# LCDTFT_FPCADPTR40T50P.net
KiCad netlist of a schematic drawn in Altium Designer
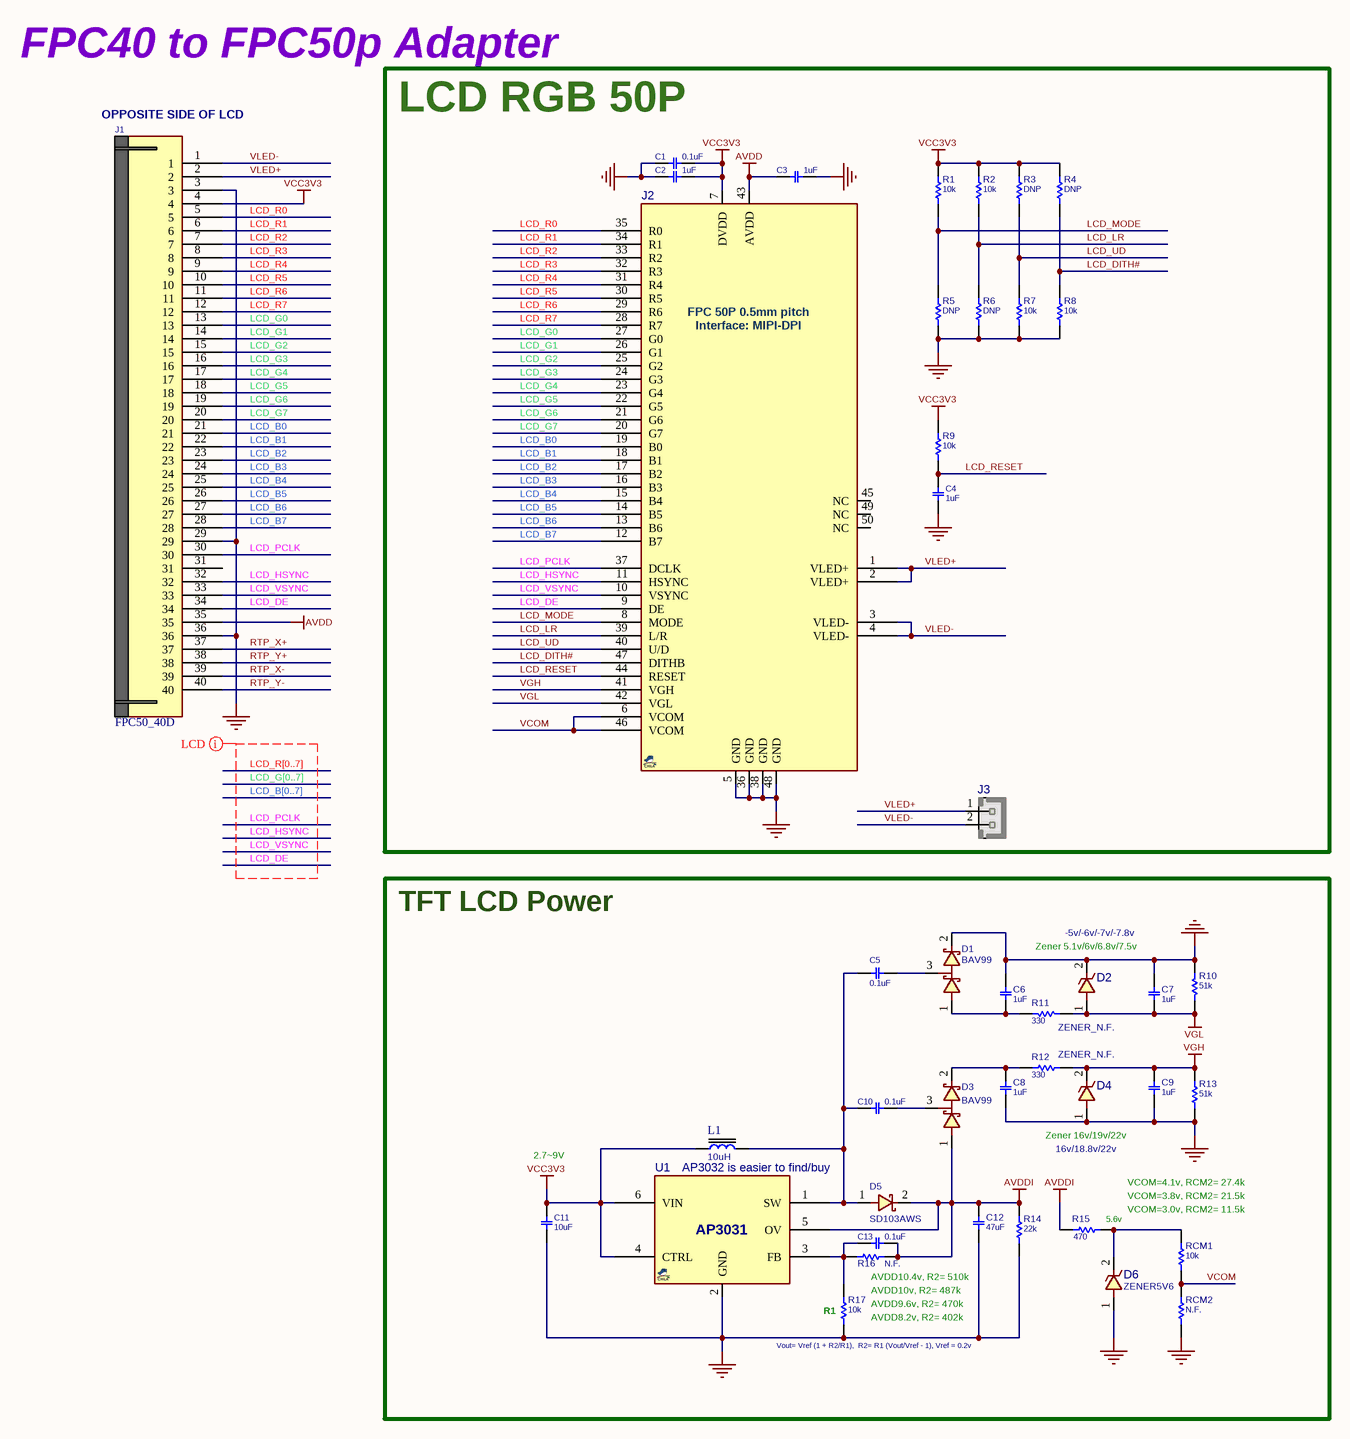
[diagram p0: LCDTFT_FPCADPTR40T50P.SchDoc]

(export (version "E")
  (design (tool "Eeschema 10.0.6"))
  (components
    (comp (ref "C1")
      (value "0.1uF")
      (footprint "C0402")
      (description "CAP, MLCC")
      (fields (field (name "MANF_P#") "GRM155R71H104KE14D") (field (name "MANF") "Murata"))
      (libsource (lib "passive_smd") (part "CAP_SMD_MLCC"))
    )
    (comp (ref "C2")
      (value "1uF")
      (footprint "C0402")
      (description "CAP, MLCC")
      (fields (field (name "MANF_P#") "CL05A105KO5NNND") (field (name "MANF") "Samsung"))
      (libsource (lib "passive_smd") (part "CAP_SMD_MLCC"))
    )
    (comp (ref "C3")
      (value "1uF")
      (footprint "C0402")
      (description "CAP, MLCC")
      (fields (field (name "MANF_P#") "CL05A105KO5NNND") (field (name "MANF") "Samsung"))
      (libsource (lib "passive_smd") (part "CAP_SMD_MLCC"))
    )
    (comp (ref "C4")
      (value "1uF")
      (footprint "C0402")
      (description "CAP, MLCC")
      (fields (field (name "MANF_P#") "CL05A105KO5NNND") (field (name "MANF") "Samsung"))
      (libsource (lib "passive_smd") (part "CAP_SMD_MLCC"))
    )
    (comp (ref "C5")
      (value "0.1uF")
      (footprint "C0402")
      (description "CAP, MLCC, 100nF, 50V, X7R, 10%, 0402C")
      (fields (field (name "MANF") "Murata") (field (name "MANF_P#") "GCM155R71H104KE02D"))
      (libsource (lib "passive_mlcc_smd") (part "CAP_SMD_MLCC_100n50V"))
    )
    (comp (ref "C6")
      (value "1uF")
      (footprint "C0603")
      (description "CAP, MLCC")
      (fields (field (name "MANF_P#") "CL10A105KB8NNNC") (field (name "MANF") "Samsung"))
      (libsource (lib "passive_smd") (part "CAP_SMD_MLCC"))
    )
    (comp (ref "C7")
      (value "1uF")
      (footprint "C0603")
      (description "CAP, MLCC")
      (fields (field (name "MANF_P#") "CL10A105KB8NNNC") (field (name "MANF") "Samsung"))
      (libsource (lib "passive_smd") (part "CAP_SMD_MLCC"))
    )
    (comp (ref "C8")
      (value "1uF")
      (footprint "C0603")
      (description "CAP, MLCC")
      (fields (field (name "MANF_P#") "CL10A105KB8NNNC") (field (name "MANF") "Samsung"))
      (libsource (lib "passive_smd") (part "CAP_SMD_MLCC"))
    )
    (comp (ref "C9")
      (value "1uF")
      (footprint "C0603")
      (description "CAP, MLCC")
      (fields (field (name "MANF_P#") "CL10A105KB8NNNC") (field (name "MANF") "Samsung"))
      (libsource (lib "passive_smd") (part "CAP_SMD_MLCC"))
    )
    (comp (ref "C10")
      (value "0.1uF")
      (footprint "C0402")
      (description "CAP, MLCC, 100nF, 50V, X7R, 10%, 0402C")
      (fields (field (name "MANF") "Murata") (field (name "MANF_P#") "GCM155R71H104KE02D"))
      (libsource (lib "passive_mlcc_smd") (part "CAP_SMD_MLCC_100n50V"))
    )
    (comp (ref "C11")
      (value "10uF")
      (footprint "C0603")
      (description "CAP, MLCC")
      (fields (field (name "MANF_P#") "CL10A106MO8NQNC") (field (name "MANF") "Samsung"))
      (libsource (lib "passive_smd") (part "CAP_SMD_MLCC"))
    )
    (comp (ref "C12")
      (value "47uF")
      (footprint "C1206")
      (description "CAP, MLCC")
      (fields (field (name "MANF_P#") "GRM31CR61E476ME44L") (field (name "MANF") "Murata"))
      (libsource (lib "passive_smd") (part "CAP_SMD_MLCC"))
    )
    (comp (ref "C13")
      (value "0.1uF")
      (footprint "C0402")
      (description "CAP, MLCC, 100nF, 50V, X7R, 10%, 0402C")
      (fields (field (name "MANF") "Murata") (field (name "MANF_P#") "GCM155R71H104KE02D"))
      (libsource (lib "passive_mlcc_smd") (part "CAP_SMD_MLCC_100n50V"))
    )
    (comp (ref "D1")
      (value "BAV99")
      (footprint "SOT23_3")
      (description "DIODE, SCHOTTKY, DUAL, 30V, 0.2A")
      (fields (field (name "MANF") "Diodes"))
      (libsource (lib "diode") (part "DIODE_SMD_SCHOTTKY_BAV99"))
    )
    (comp (ref "D2")
      (value "ZENER_N.F.")
      (footprint "D_SOD123W")
      (description "DIODE, ZENER, 0.5W")
      (fields (field (name "MANF") "Diodes"))
      (libsource (lib "diode") (part "DIODE_SMD_ZENER_DFLZ5V1"))
    )
    (comp (ref "D3")
      (value "BAV99")
      (footprint "SOT23_3")
      (description "DIODE, SCHOTTKY, DUAL, 30V, 0.2A")
      (fields (field (name "MANF") "Diodes"))
      (libsource (lib "diode") (part "DIODE_SMD_SCHOTTKY_BAV99"))
    )
    (comp (ref "D4")
      (value "ZENER_N.F.")
      (footprint "D_SOD123W")
      (description "DIODE, ZENER, 0.5W")
      (fields (field (name "MANF") "Diodes"))
      (libsource (lib "diode") (part "DIODE_SMD_ZENER_DFLZ5V1"))
    )
    (comp (ref "D5")
      (value "SD103AWS")
      (footprint "D_SOD323")
      (description "DIODE, SCHOTTKY, 40V, 2A")
      (fields (field (name "MANF") "DIODES"))
      (libsource (lib "diode") (part "DIODE_SMD_SCHOTTKY_1N5819"))
    )
    (comp (ref "D6")
      (value "ZENER5V6")
      (footprint "D_SOD123W")
      (description "DIODE, ZENER, 0.5W")
      (fields (field (name "MANF") "Diodes"))
      (libsource (lib "diode") (part "DIODE_SMD_ZENER_DFLZ5V1"))
    )
    (comp (ref "J1")
      (value "FPC50_40D")
      (footprint "FPC50_40D_FFC2B29")
      (description "CONN, FPC, 0.50mm pitch, RightAngle, Dual side Contact")
      (fields (field (name "MANF") "GCT") (field (name "MANF_P#") "FFC2B29-40-G"))
      (libsource (lib "conn_fpc") (part "FPC50_40D_FFC2B29"))
    )
    (comp (ref "J2")
      (value "FPC_50_0.5mm")
      (footprint "FPC50_50T")
      (description "LCD TFT Color, FPC50P, RGB")
      (libsource (lib "lcdtft") (part "LCDTFT_DPI_FPC50P"))
    )
    (comp (ref "J3")
      (value "HHDR_2")
      (footprint "ER_CON3P5_2_SMD")
      (description "JST-XH pitch: 2.5mm")
      (libsource (lib "conn_wire2board") (part "XH_2"))
    )
    (comp (ref "L1")
      (value "10uH")
      (footprint "L_4")
      (description "INDUCTOR, POWER, SMD")
      (fields (field (name "MANF_P#") "GCD43-100MC"))
      (libsource (lib "passive") (part "INDPWR_SMD"))
    )
    (comp (ref "R1")
      (value "10k")
      (footprint "R0402")
      (description "RESISTOR, SMD")
      (libsource (lib "passive_res_smd") (part "RES_SMD"))
    )
    (comp (ref "R2")
      (value "10k")
      (footprint "R0402")
      (description "RESISTOR, SMD")
      (libsource (lib "passive_res_smd") (part "RES_SMD"))
    )
    (comp (ref "R3")
      (value "DNP")
      (footprint "R0402")
      (description "RESISTOR, SMD")
      (libsource (lib "passive_res_smd") (part "RES_SMD"))
    )
    (comp (ref "R4")
      (value "DNP")
      (footprint "R0402")
      (description "RESISTOR, SMD")
      (libsource (lib "passive_res_smd") (part "RES_SMD"))
    )
    (comp (ref "R5")
      (value "DNP")
      (footprint "R0402")
      (description "RESISTOR, SMD")
      (libsource (lib "passive_res_smd") (part "RES_SMD"))
    )
    (comp (ref "R6")
      (value "DNP")
      (footprint "R0402")
      (description "RESISTOR, SMD")
      (libsource (lib "passive_res_smd") (part "RES_SMD"))
    )
    (comp (ref "R7")
      (value "10k")
      (footprint "R0402")
      (description "RESISTOR, SMD")
      (libsource (lib "passive_res_smd") (part "RES_SMD"))
    )
    (comp (ref "R8")
      (value "10k")
      (footprint "R0402")
      (description "RESISTOR, SMD")
      (libsource (lib "passive_res_smd") (part "RES_SMD"))
    )
    (comp (ref "R9")
      (value "10k")
      (footprint "R0402")
      (description "RESISTOR, SMD")
      (libsource (lib "passive_res_smd") (part "RES_SMD"))
    )
    (comp (ref "R10")
      (value "51k")
      (footprint "R0402")
      (description "RESISTOR, SMD, 20K, 0402")
      (fields (field (name "MANF") "Yageo") (field (name "MANF_P#") "RK73H1ETTP2002F"))
      (libsource (lib "chila_passive") (part "RES_SMD"))
    )
    (comp (ref "R11")
      (value "330")
      (footprint "R0402")
      (description "RESISTOR, SMD, 20K, 0402")
      (fields (field (name "MANF") "Yageo") (field (name "MANF_P#") "RK73H1ETTP2002F"))
      (libsource (lib "chila_passive") (part "RES_SMD"))
    )
    (comp (ref "R12")
      (value "330")
      (footprint "R0402")
      (description "RESISTOR, SMD, 20K, 0402")
      (fields (field (name "MANF") "Yageo") (field (name "MANF_P#") "RK73H1ETTP2002F"))
      (libsource (lib "chila_passive") (part "RES_SMD"))
    )
    (comp (ref "R13")
      (value "51k")
      (footprint "R0402")
      (description "RESISTOR, SMD, 20K, 0402")
      (fields (field (name "MANF") "Yageo") (field (name "MANF_P#") "RK73H1ETTP2002F"))
      (libsource (lib "chila_passive") (part "RES_SMD"))
    )
    (comp (ref "R14")
      (value "22k")
      (footprint "R0402")
      (description "RESISTOR, SMD, 20K, 0402")
      (fields (field (name "MANF") "Yageo") (field (name "MANF_P#") "RK73H1ETTP2002F"))
      (libsource (lib "chila_passive") (part "RES_SMD"))
    )
    (comp (ref "R15")
      (value "470")
      (footprint "R0402")
      (description "RESISTOR, SMD, 20K, 0402")
      (fields (field (name "MANF") "Yageo") (field (name "MANF_P#") "RK73H1ETTP2002F"))
      (libsource (lib "chila_passive") (part "RES_SMD"))
    )
    (comp (ref "R16")
      (value "N.F.")
      (footprint "R0402")
      (description "RESISTOR, SMD, 20K, 0402")
      (fields (field (name "MANF") "Yageo") (field (name "MANF_P#") "RK73H1ETTP2002F"))
      (libsource (lib "chila_passive") (part "RES_SMD"))
    )
    (comp (ref "R17")
      (value "10k")
      (footprint "R0402")
      (description "RESISTOR, SMD, 20K, 0402")
      (fields (field (name "MANF") "Yageo") (field (name "MANF_P#") "RK73H1ETTP2002F"))
      (libsource (lib "chila_passive") (part "RES_SMD"))
    )
    (comp (ref "RCM1")
      (value "10k")
      (footprint "R0402")
      (description "RESISTOR, SMD, 20K, 0402")
      (fields (field (name "MANF") "Yageo") (field (name "MANF_P#") "RK73H1ETTP2002F"))
      (libsource (lib "chila_passive") (part "RES_SMD"))
    )
    (comp (ref "RCM2")
      (value "N.F.")
      (footprint "R0402")
      (description "RESISTOR, SMD, 20K, 0402")
      (fields (field (name "MANF") "Yageo") (field (name "MANF_P#") "RK73H1ETTP2002F"))
      (libsource (lib "chila_passive") (part "RES_SMD"))
    )
    (comp (ref "U1")
      (value "AP3031")
      (footprint "SOT23_6")
      (description "REG, Switching, Boost, 1.4A, ADJ, 1MHz, SOT-23-6")
      (fields (field (name "MANF_P#") "AP3031K") (field (name "MANF") "Diodes"))
      (libsource (lib "pwr_switching_boost") (part "VREG_AP3031_SOT23"))
    )
  )
  (nets
    (net (code "1") (name "/LCD_B0") (class "Default")
      (node (ref "J1") (pin "21") (pinfunction "21_21") (pintype "passive"))
      (node (ref "J2") (pin "19") (pinfunction "B0_19") (pintype "passive"))
    )
    (net (code "2") (name "/LCD_B1") (class "Default")
      (node (ref "J1") (pin "22") (pinfunction "22_22") (pintype "passive"))
      (node (ref "J2") (pin "18") (pinfunction "B1_18") (pintype "passive"))
    )
    (net (code "3") (name "/LCD_B2") (class "Default")
      (node (ref "J1") (pin "23") (pinfunction "23_23") (pintype "passive"))
      (node (ref "J2") (pin "17") (pinfunction "B2_17") (pintype "passive"))
    )
    (net (code "4") (name "/LCD_B3") (class "Default")
      (node (ref "J1") (pin "24") (pinfunction "24_24") (pintype "passive"))
      (node (ref "J2") (pin "16") (pinfunction "B3_16") (pintype "passive"))
    )
    (net (code "5") (name "/LCD_B4") (class "Default")
      (node (ref "J1") (pin "25") (pinfunction "25_25") (pintype "passive"))
      (node (ref "J2") (pin "15") (pinfunction "B4_15") (pintype "passive"))
    )
    (net (code "6") (name "/LCD_B5") (class "Default")
      (node (ref "J1") (pin "26") (pinfunction "26_26") (pintype "passive"))
      (node (ref "J2") (pin "14") (pinfunction "B5_14") (pintype "passive"))
    )
    (net (code "7") (name "/LCD_B6") (class "Default")
      (node (ref "J1") (pin "27") (pinfunction "27_27") (pintype "passive"))
      (node (ref "J2") (pin "13") (pinfunction "B6_13") (pintype "passive"))
    )
    (net (code "8") (name "/LCD_B7") (class "Default")
      (node (ref "J1") (pin "28") (pinfunction "28_28") (pintype "passive"))
      (node (ref "J2") (pin "12") (pinfunction "B7_12") (pintype "passive"))
    )
    (net (code "10") (name "/LCD_DE") (class "Default")
      (node (ref "J1") (pin "34") (pinfunction "34_34") (pintype "passive"))
      (node (ref "J2") (pin "9") (pinfunction "DE_9") (pintype "passive"))
    )
    (net (code "11") (name "/LCD_DITH#") (class "Default")
      (node (ref "J2") (pin "47") (pinfunction "DITHB_47") (pintype "passive"))
      (node (ref "R4") (pin "2") (pinfunction "2_2") (pintype "passive"))
      (node (ref "R8") (pin "1") (pinfunction "1_1") (pintype "passive"))
    )
    (net (code "12") (name "/LCD_G0") (class "Default")
      (node (ref "J1") (pin "13") (pinfunction "13_13") (pintype "passive"))
      (node (ref "J2") (pin "27") (pinfunction "G0_27") (pintype "passive"))
    )
    (net (code "13") (name "/LCD_G1") (class "Default")
      (node (ref "J1") (pin "14") (pinfunction "14_14") (pintype "passive"))
      (node (ref "J2") (pin "26") (pinfunction "G1_26") (pintype "passive"))
    )
    (net (code "14") (name "/LCD_G2") (class "Default")
      (node (ref "J1") (pin "15") (pinfunction "15_15") (pintype "passive"))
      (node (ref "J2") (pin "25") (pinfunction "G2_25") (pintype "passive"))
    )
    (net (code "15") (name "/LCD_G3") (class "Default")
      (node (ref "J1") (pin "16") (pinfunction "16_16") (pintype "passive"))
      (node (ref "J2") (pin "24") (pinfunction "G3_24") (pintype "passive"))
    )
    (net (code "16") (name "/LCD_G4") (class "Default")
      (node (ref "J1") (pin "17") (pinfunction "17_17") (pintype "passive"))
      (node (ref "J2") (pin "23") (pinfunction "G4_23") (pintype "passive"))
    )
    (net (code "17") (name "/LCD_G5") (class "Default")
      (node (ref "J1") (pin "18") (pinfunction "18_18") (pintype "passive"))
      (node (ref "J2") (pin "22") (pinfunction "G5_22") (pintype "passive"))
    )
    (net (code "18") (name "/LCD_G6") (class "Default")
      (node (ref "J1") (pin "19") (pinfunction "19_19") (pintype "passive"))
      (node (ref "J2") (pin "21") (pinfunction "G6_21") (pintype "passive"))
    )
    (net (code "19") (name "/LCD_G7") (class "Default")
      (node (ref "J1") (pin "20") (pinfunction "20_20") (pintype "passive"))
      (node (ref "J2") (pin "20") (pinfunction "G7_20") (pintype "passive"))
    )
    (net (code "21") (name "/LCD_HSYNC") (class "Default")
      (node (ref "J1") (pin "32") (pinfunction "32_32") (pintype "passive"))
      (node (ref "J2") (pin "11") (pinfunction "HSYNC_11") (pintype "passive"))
    )
    (net (code "22") (name "/LCD_LR") (class "Default")
      (node (ref "J2") (pin "39") (pinfunction "L/R_39") (pintype "passive"))
      (node (ref "R2") (pin "2") (pinfunction "2_2") (pintype "passive"))
      (node (ref "R6") (pin "1") (pinfunction "1_1") (pintype "passive"))
    )
    (net (code "23") (name "/LCD_MODE") (class "Default")
      (node (ref "J2") (pin "8") (pinfunction "MODE_8") (pintype "passive"))
      (node (ref "R1") (pin "2") (pinfunction "2_2") (pintype "passive"))
      (node (ref "R5") (pin "1") (pinfunction "1_1") (pintype "passive"))
    )
    (net (code "24") (name "/LCD_PCLK") (class "Default")
      (node (ref "J1") (pin "30") (pinfunction "30_30") (pintype "passive"))
      (node (ref "J2") (pin "37") (pinfunction "DCLK_37") (pintype "passive"))
    )
    (net (code "25") (name "/LCD_R0") (class "Default")
      (node (ref "J1") (pin "5") (pinfunction "5_5") (pintype "passive"))
      (node (ref "J2") (pin "35") (pinfunction "R0_35") (pintype "passive"))
    )
    (net (code "26") (name "/LCD_R1") (class "Default")
      (node (ref "J1") (pin "6") (pinfunction "6_6") (pintype "passive"))
      (node (ref "J2") (pin "34") (pinfunction "R1_34") (pintype "passive"))
    )
    (net (code "27") (name "/LCD_R2") (class "Default")
      (node (ref "J1") (pin "7") (pinfunction "7_7") (pintype "passive"))
      (node (ref "J2") (pin "33") (pinfunction "R2_33") (pintype "passive"))
    )
    (net (code "28") (name "/LCD_R3") (class "Default")
      (node (ref "J1") (pin "8") (pinfunction "8_8") (pintype "passive"))
      (node (ref "J2") (pin "32") (pinfunction "R3_32") (pintype "passive"))
    )
    (net (code "29") (name "/LCD_R4") (class "Default")
      (node (ref "J1") (pin "9") (pinfunction "9_9") (pintype "passive"))
      (node (ref "J2") (pin "31") (pinfunction "R4_31") (pintype "passive"))
    )
    (net (code "30") (name "/LCD_R5") (class "Default")
      (node (ref "J1") (pin "10") (pinfunction "10_10") (pintype "passive"))
      (node (ref "J2") (pin "30") (pinfunction "R5_30") (pintype "passive"))
    )
    (net (code "31") (name "/LCD_R6") (class "Default")
      (node (ref "J1") (pin "11") (pinfunction "11_11") (pintype "passive"))
      (node (ref "J2") (pin "29") (pinfunction "R6_29") (pintype "passive"))
    )
    (net (code "32") (name "/LCD_R7") (class "Default")
      (node (ref "J1") (pin "12") (pinfunction "12_12") (pintype "passive"))
      (node (ref "J2") (pin "28") (pinfunction "R7_28") (pintype "passive"))
    )
    (net (code "33") (name "/LCD_RESET") (class "Default")
      (node (ref "C4") (pin "1") (pinfunction "1_1") (pintype "passive"))
      (node (ref "J2") (pin "44") (pinfunction "RESET_44") (pintype "passive"))
      (node (ref "R9") (pin "2") (pinfunction "2_2") (pintype "passive"))
    )
    (net (code "35") (name "/LCD_UD") (class "Default")
      (node (ref "J2") (pin "40") (pinfunction "U/D_40") (pintype "passive"))
      (node (ref "R3") (pin "2") (pinfunction "2_2") (pintype "passive"))
      (node (ref "R7") (pin "1") (pinfunction "1_1") (pintype "passive"))
    )
    (net (code "36") (name "/LCD_VSYNC") (class "Default")
      (node (ref "J1") (pin "33") (pinfunction "33_33") (pintype "passive"))
      (node (ref "J2") (pin "10") (pinfunction "VSYNC_10") (pintype "passive"))
    )
    (net (code "37") (name "/RTP_X+") (class "Default")
      (node (ref "J1") (pin "37") (pinfunction "37_37") (pintype "passive"))
    )
    (net (code "38") (name "/RTP_X-") (class "Default")
      (node (ref "J1") (pin "39") (pinfunction "39_39") (pintype "passive"))
    )
    (net (code "39") (name "/RTP_Y+") (class "Default")
      (node (ref "J1") (pin "38") (pinfunction "38_38") (pintype "passive"))
    )
    (net (code "40") (name "/RTP_Y-") (class "Default")
      (node (ref "J1") (pin "40") (pinfunction "40_40") (pintype "passive"))
    )
    (net (code "41") (name "/VCOM") (class "Default")
      (node (ref "J2") (pin "46") (pinfunction "VCOM_46") (pintype "passive"))
      (node (ref "J2") (pin "6") (pinfunction "VCOM_6") (pintype "passive"))
      (node (ref "RCM1") (pin "2") (pinfunction "2_2") (pintype "passive"))
      (node (ref "RCM2") (pin "1") (pinfunction "1_1") (pintype "passive"))
    )
    (net (code "42") (name "/VLED+") (class "Default")
      (node (ref "J1") (pin "2") (pinfunction "2_2") (pintype "passive"))
      (node (ref "J2") (pin "1") (pinfunction "VLED+_1") (pintype "passive"))
      (node (ref "J2") (pin "2") (pinfunction "VLED+_2") (pintype "passive"))
      (node (ref "J3") (pin "1") (pinfunction "1_1") (pintype "passive"))
    )
    (net (code "43") (name "/VLED-") (class "Default")
      (node (ref "J1") (pin "1") (pinfunction "1_1") (pintype "passive"))
      (node (ref "J2") (pin "3") (pinfunction "VLED-_3") (pintype "passive"))
      (node (ref "J2") (pin "4") (pinfunction "VLED-_4") (pintype "passive"))
      (node (ref "J3") (pin "2") (pinfunction "2_2") (pintype "passive"))
    )
    (net (code "44") (name "AVDD") (class "Default")
      (node (ref "C3") (pin "2") (pinfunction "2_2") (pintype "passive"))
      (node (ref "J1") (pin "35") (pinfunction "35_35") (pintype "passive"))
      (node (ref "J2") (pin "43") (pinfunction "AVDD_43") (pintype "passive"))
    )
    (net (code "45") (name "AVDDI") (class "Default")
      (node (ref "C12") (pin "2") (pinfunction "2_2") (pintype "passive"))
      (node (ref "C13") (pin "1") (pinfunction "1_1") (pintype "passive"))
      (node (ref "D3") (pin "1") (pinfunction "1_1") (pintype "passive"))
      (node (ref "D5") (pin "2") (pinfunction "2_2") (pintype "passive"))
      (node (ref "R14") (pin "1") (pinfunction "1_1") (pintype "passive"))
      (node (ref "R15") (pin "1") (pinfunction "1_1") (pintype "passive"))
      (node (ref "R16") (pin "2") (pinfunction "2_2") (pintype "passive"))
      (node (ref "U1") (pin "5") (pinfunction "OV_5") (pintype "passive"))
    )
    (net (code "46") (name "GND") (class "Default")
      (node (ref "C1") (pin "2") (pinfunction "2_2") (pintype "passive"))
      (node (ref "C11") (pin "1") (pinfunction "1_1") (pintype "passive"))
      (node (ref "C12") (pin "1") (pinfunction "1_1") (pintype "passive"))
      (node (ref "C2") (pin "2") (pinfunction "2_2") (pintype "passive"))
      (node (ref "C3") (pin "1") (pinfunction "1_1") (pintype "passive"))
      (node (ref "C4") (pin "2") (pinfunction "2_2") (pintype "passive"))
      (node (ref "C6") (pin "1") (pinfunction "1_1") (pintype "passive"))
      (node (ref "C7") (pin "1") (pinfunction "1_1") (pintype "passive"))
      (node (ref "C8") (pin "1") (pinfunction "1_1") (pintype "passive"))
      (node (ref "C9") (pin "1") (pinfunction "1_1") (pintype "passive"))
      (node (ref "D1") (pin "2") (pinfunction "2_2") (pintype "passive"))
      (node (ref "D2") (pin "2") (pinfunction "2_2") (pintype "passive"))
      (node (ref "D4") (pin "1") (pinfunction "1_1") (pintype "passive"))
      (node (ref "D6") (pin "1") (pinfunction "1_1") (pintype "passive"))
      (node (ref "J1") (pin "29") (pinfunction "29_29") (pintype "passive"))
      (node (ref "J1") (pin "3") (pinfunction "3_3") (pintype "passive"))
      (node (ref "J1") (pin "36") (pinfunction "36_36") (pintype "passive"))
      (node (ref "J2") (pin "36") (pinfunction "GND_36") (pintype "passive"))
      (node (ref "J2") (pin "38") (pinfunction "GND_38") (pintype "passive"))
      (node (ref "J2") (pin "48") (pinfunction "GND_48") (pintype "passive"))
      (node (ref "J2") (pin "5") (pinfunction "GND_5") (pintype "passive"))
      (node (ref "R10") (pin "1") (pinfunction "1_1") (pintype "passive"))
      (node (ref "R13") (pin "1") (pinfunction "1_1") (pintype "passive"))
      (node (ref "R14") (pin "2") (pinfunction "2_2") (pintype "passive"))
      (node (ref "R17") (pin "2") (pinfunction "2_2") (pintype "passive"))
      (node (ref "R5") (pin "2") (pinfunction "2_2") (pintype "passive"))
      (node (ref "R6") (pin "2") (pinfunction "2_2") (pintype "passive"))
      (node (ref "R7") (pin "2") (pinfunction "2_2") (pintype "passive"))
      (node (ref "R8") (pin "2") (pinfunction "2_2") (pintype "passive"))
      (node (ref "RCM2") (pin "2") (pinfunction "2_2") (pintype "passive"))
      (node (ref "U1") (pin "2") (pinfunction "GND_2") (pintype "tri_state"))
    )
    (net (code "47") (name "Net-(C5-Pad1)") (class "Default")
      (node (ref "C5") (pin "1") (pinfunction "1_1") (pintype "passive"))
      (node (ref "D1") (pin "3") (pinfunction "3_3") (pintype "passive"))
    )
    (net (code "48") (name "Net-(C6-Pad2)") (class "Default")
      (node (ref "C6") (pin "2") (pinfunction "2_2") (pintype "passive"))
      (node (ref "D1") (pin "1") (pinfunction "1_1") (pintype "passive"))
      (node (ref "R11") (pin "1") (pinfunction "1_1") (pintype "passive"))
    )
    (net (code "49") (name "Net-(C8-Pad2)") (class "Default")
      (node (ref "C8") (pin "2") (pinfunction "2_2") (pintype "passive"))
      (node (ref "D3") (pin "2") (pinfunction "2_2") (pintype "passive"))
      (node (ref "R12") (pin "1") (pinfunction "1_1") (pintype "passive"))
    )
    (net (code "50") (name "Net-(C10-Pad1)") (class "Default")
      (node (ref "C10") (pin "1") (pinfunction "1_1") (pintype "passive"))
      (node (ref "D3") (pin "3") (pinfunction "3_3") (pintype "passive"))
    )
    (net (code "51") (name "Net-(D6-Pad2)") (class "Default")
      (node (ref "D6") (pin "2") (pinfunction "2_2") (pintype "passive"))
      (node (ref "R15") (pin "2") (pinfunction "2_2") (pintype "passive"))
      (node (ref "RCM1") (pin "1") (pinfunction "1_1") (pintype "passive"))
    )
    (net (code "52") (name "Net-(U1-FB)") (class "Default")
      (node (ref "C13") (pin "2") (pinfunction "2_2") (pintype "passive"))
      (node (ref "R16") (pin "1") (pinfunction "1_1") (pintype "passive"))
      (node (ref "R17") (pin "1") (pinfunction "1_1") (pintype "passive"))
      (node (ref "U1") (pin "3") (pinfunction "FB_3") (pintype "passive"))
    )
    (net (code "53") (name "Net-(U1-SW)") (class "Default")
      (node (ref "C10") (pin "2") (pinfunction "2_2") (pintype "passive"))
      (node (ref "C5") (pin "2") (pinfunction "2_2") (pintype "passive"))
      (node (ref "D5") (pin "1") (pinfunction "1_1") (pintype "passive"))
      (node (ref "L1") (pin "2") (pinfunction "2_2") (pintype "passive"))
      (node (ref "U1") (pin "1") (pinfunction "SW_1") (pintype "passive"))
    )
    (net (code "54") (name "VCC3V3") (class "Default")
      (node (ref "C1") (pin "1") (pinfunction "1_1") (pintype "passive"))
      (node (ref "C11") (pin "2") (pinfunction "2_2") (pintype "passive"))
      (node (ref "C2") (pin "1") (pinfunction "1_1") (pintype "passive"))
      (node (ref "J1") (pin "4") (pinfunction "4_4") (pintype "passive"))
      (node (ref "J2") (pin "7") (pinfunction "DVDD_7") (pintype "passive"))
      (node (ref "L1") (pin "1") (pinfunction "1_1") (pintype "passive"))
      (node (ref "R1") (pin "1") (pinfunction "1_1") (pintype "passive"))
      (node (ref "R2") (pin "1") (pinfunction "1_1") (pintype "passive"))
      (node (ref "R3") (pin "1") (pinfunction "1_1") (pintype "passive"))
      (node (ref "R4") (pin "1") (pinfunction "1_1") (pintype "passive"))
      (node (ref "R9") (pin "1") (pinfunction "1_1") (pintype "passive"))
      (node (ref "U1") (pin "4") (pinfunction "CTRL_4") (pintype "passive"))
      (node (ref "U1") (pin "6") (pinfunction "VIN_6") (pintype "passive"))
    )
    (net (code "55") (name "VGH") (class "Default")
      (node (ref "C9") (pin "2") (pinfunction "2_2") (pintype "passive"))
      (node (ref "D4") (pin "2") (pinfunction "2_2") (pintype "passive"))
      (node (ref "J2") (pin "41") (pinfunction "VGH_41") (pintype "passive"))
      (node (ref "R12") (pin "2") (pinfunction "2_2") (pintype "passive"))
      (node (ref "R13") (pin "2") (pinfunction "2_2") (pintype "passive"))
    )
    (net (code "56") (name "VGL") (class "Default")
      (node (ref "C7") (pin "2") (pinfunction "2_2") (pintype "passive"))
      (node (ref "D2") (pin "1") (pinfunction "1_1") (pintype "passive"))
      (node (ref "J2") (pin "42") (pinfunction "VGL_42") (pintype "passive"))
      (node (ref "R10") (pin "2") (pinfunction "2_2") (pintype "passive"))
      (node (ref "R11") (pin "2") (pinfunction "2_2") (pintype "passive"))
    )
    (net (code "57") (name "unconnected-(J1-Pad31)") (class "Default")
      (node (ref "J1") (pin "31") (pinfunction "31_31") (pintype "passive"))
    )
    (net (code "58") (name "unconnected-(J2-NC-Pad45)") (class "Default")
      (node (ref "J2") (pin "45") (pinfunction "NC_45") (pintype "passive"))
    )
    (net (code "59") (name "unconnected-(J2-NC-Pad49)") (class "Default")
      (node (ref "J2") (pin "49") (pinfunction "NC_49") (pintype "passive"))
    )
    (net (code "60") (name "unconnected-(J2-NC-Pad50)") (class "Default")
      (node (ref "J2") (pin "50") (pinfunction "NC_50") (pintype "passive"))
    )
  )
)
